# car_bt.net
KiCad netlist of a schematic drawn in EAGLE
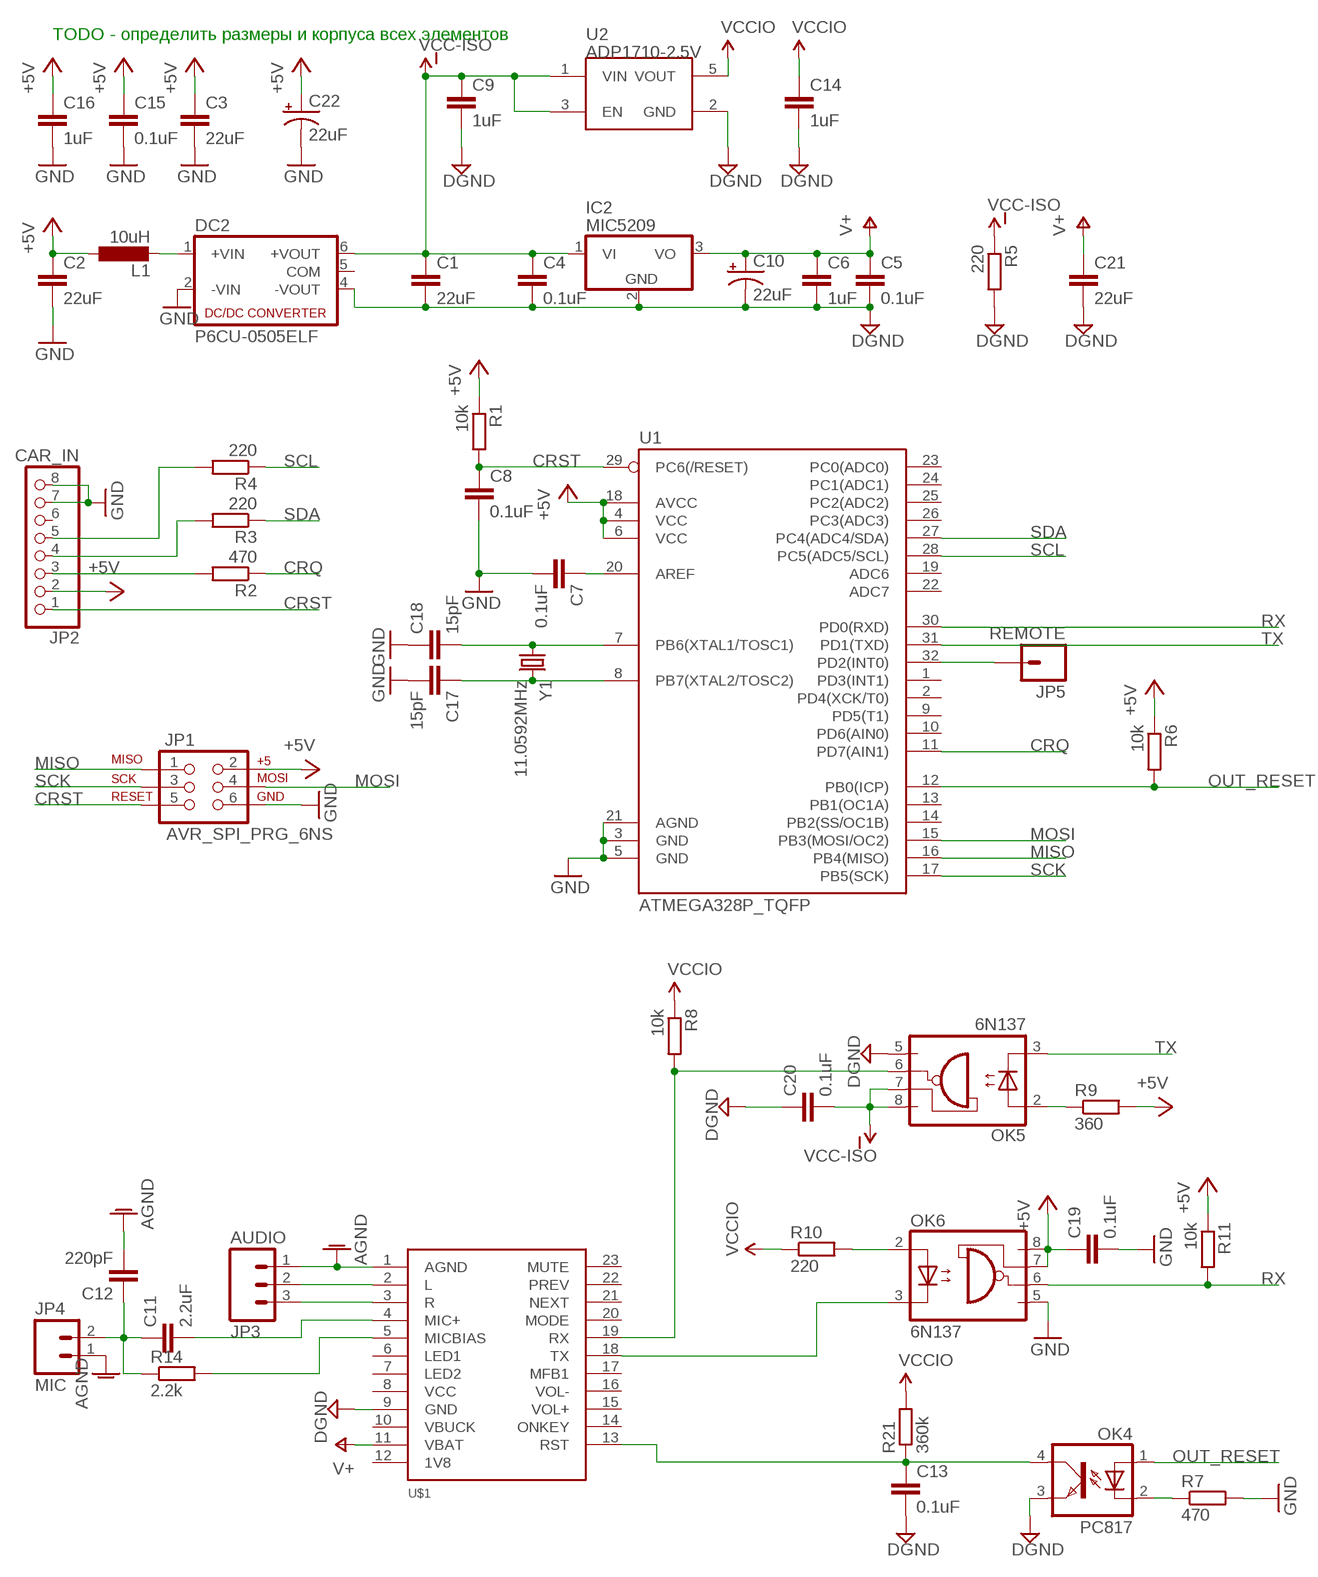
[diagram p0: schematic, sheet 1]

(export (version "E")
  (design (tool "Eeschema 10.0.6"))
  (components
    (comp (ref "C1")
      (value "22uF")
      (footprint "eagle-import:C1206")
      (libsource (lib "eagle-import") (part "C-EUC1206"))
    )
    (comp (ref "C2")
      (value "22uF")
      (footprint "eagle-import:C1206")
      (libsource (lib "eagle-import") (part "C-EUC1206"))
    )
    (comp (ref "C3")
      (value "22uF")
      (footprint "eagle-import:C1206")
      (libsource (lib "eagle-import") (part "C-EUC1206"))
    )
    (comp (ref "C4")
      (value "0.1uF")
      (footprint "eagle-import:C0805")
      (libsource (lib "eagle-import") (part "C-EUC0805"))
    )
    (comp (ref "C5")
      (value "0.1uF")
      (footprint "eagle-import:C0805")
      (libsource (lib "eagle-import") (part "C-EUC0805"))
    )
    (comp (ref "C6")
      (value "1uF")
      (footprint "eagle-import:C0805")
      (libsource (lib "eagle-import") (part "C-EUC0805"))
    )
    (comp (ref "C7")
      (value "0.1uF")
      (footprint "eagle-import:C0805")
      (libsource (lib "eagle-import") (part "C-EUC0805"))
    )
    (comp (ref "C8")
      (value "0.1uF")
      (footprint "eagle-import:C0805")
      (libsource (lib "eagle-import") (part "C-EUC0805"))
    )
    (comp (ref "C9")
      (value "1uF")
      (footprint "eagle-import:C0805")
      (libsource (lib "eagle-import") (part "C-EUC0805"))
    )
    (comp (ref "C10")
      (value "22uF")
      (footprint "eagle-import:EIA3528")
      (libsource (lib "eagle-import") (part "CAP_POL3528"))
    )
    (comp (ref "C11")
      (value "2.2uF")
      (footprint "eagle-import:C0805")
      (libsource (lib "eagle-import") (part "C-EUC0805"))
    )
    (comp (ref "C12")
      (value "220pF")
      (footprint "eagle-import:C0805")
      (libsource (lib "eagle-import") (part "C-EUC0805"))
    )
    (comp (ref "C13")
      (value "0.1uF")
      (footprint "eagle-import:C0805")
      (libsource (lib "eagle-import") (part "C-EUC0805"))
    )
    (comp (ref "C14")
      (value "1uF")
      (footprint "eagle-import:C0805")
      (libsource (lib "eagle-import") (part "C-EUC0805"))
    )
    (comp (ref "C15")
      (value "0.1uF")
      (footprint "eagle-import:C0805")
      (libsource (lib "eagle-import") (part "C-EUC0805"))
    )
    (comp (ref "C16")
      (value "1uF")
      (footprint "eagle-import:C0805")
      (libsource (lib "eagle-import") (part "C-EUC0805"))
    )
    (comp (ref "C17")
      (value "15pF")
      (footprint "eagle-import:C0805")
      (libsource (lib "eagle-import") (part "C-EUC0805"))
    )
    (comp (ref "C18")
      (value "15pF")
      (footprint "eagle-import:C0805")
      (libsource (lib "eagle-import") (part "C-EUC0805"))
    )
    (comp (ref "C19")
      (value "0.1uF")
      (footprint "eagle-import:C0805")
      (libsource (lib "eagle-import") (part "C-EUC0805"))
    )
    (comp (ref "C20")
      (value "0.1uF")
      (footprint "eagle-import:C0805")
      (libsource (lib "eagle-import") (part "C-EUC0805"))
    )
    (comp (ref "C21")
      (value "22uF")
      (footprint "eagle-import:C1206")
      (libsource (lib "eagle-import") (part "C-EUC1206"))
    )
    (comp (ref "C22")
      (value "22uF")
      (footprint "eagle-import:EIA3528")
      (libsource (lib "eagle-import") (part "CAP_POL3528"))
    )
    (comp (ref "DC2")
      (value "P6CU-0505ELF")
      (footprint "eagle-import:NMA")
      (fields (field (name "MF") "C & D TECHNOLOGIES, INC") (field (name "MPN") "NMA0515SC"))
      (libsource (lib "eagle-import") (part "NMA"))
    )
    (comp (ref "IC2")
      (value "MIC5209")
      (footprint "eagle-import:SOT223")
      (libsource (lib "eagle-import") (part "MCP1703DB"))
    )
    (comp (ref "JP1")
      (value "AVR_SPI_PRG_6NS")
      (footprint "eagle-import:2X3-NS")
      (libsource (lib "eagle-import") (part "AVR_SPI_PRG_6NS"))
    )
    (comp (ref "JP2")
      (value "CAR_IN")
      (footprint "eagle-import:1X08_90")
      (libsource (lib "eagle-import") (part "PINHD-1X8/90"))
    )
    (comp (ref "JP3")
      (value "AUDIO")
      (footprint "eagle-import:MOLEX-1X3")
      (libsource (lib "eagle-import") (part "M03POLAR"))
    )
    (comp (ref "JP4")
      (value "MIC")
      (footprint "eagle-import:MOLEX-1X2_LOCK")
      (libsource (lib "eagle-import") (part "M02POLAR_LOCK"))
    )
    (comp (ref "JP5")
      (value "REMOTE")
      (footprint "eagle-import:1X01_LONGPAD")
      (libsource (lib "eagle-import") (part "M01PTH_LONGPAD"))
    )
    (comp (ref "L1")
      (value "10uH")
      (footprint "eagle-import:L3216C")
      (libsource (lib "eagle-import") (part "L-EUL3216C"))
    )
    (comp (ref "OK4")
      (value "PC817")
      (footprint "eagle-import:DIL04")
      (fields (field (name "MPN") "PC817X4J000F"))
      (libsource (lib "eagle-import") (part "PC817"))
    )
    (comp (ref "OK5")
      (value "6N137")
      (footprint "eagle-import:DIL08")
      (libsource (lib "eagle-import") (part "6N137"))
    )
    (comp (ref "OK6")
      (value "6N137")
      (footprint "eagle-import:DIL08")
      (libsource (lib "eagle-import") (part "6N137"))
    )
    (comp (ref "R1")
      (value "10k")
      (footprint "eagle-import:R0805")
      (libsource (lib "eagle-import") (part "R-EU_R0805"))
    )
    (comp (ref "R2")
      (value "470")
      (footprint "eagle-import:R0805")
      (libsource (lib "eagle-import") (part "R-EU_R0805"))
    )
    (comp (ref "R3")
      (value "220")
      (footprint "eagle-import:R0805")
      (libsource (lib "eagle-import") (part "R-EU_R0805"))
    )
    (comp (ref "R4")
      (value "220")
      (footprint "eagle-import:R0805")
      (libsource (lib "eagle-import") (part "R-EU_R0805"))
    )
    (comp (ref "R5")
      (value "220")
      (footprint "eagle-import:R0805")
      (libsource (lib "eagle-import") (part "R-EU_R0805"))
    )
    (comp (ref "R6")
      (value "10k")
      (footprint "eagle-import:R0805")
      (libsource (lib "eagle-import") (part "R-EU_R0805"))
    )
    (comp (ref "R7")
      (value "470")
      (footprint "eagle-import:R0805")
      (libsource (lib "eagle-import") (part "R-EU_R0805"))
    )
    (comp (ref "R8")
      (value "10k")
      (footprint "eagle-import:R0805")
      (libsource (lib "eagle-import") (part "R-EU_R0805"))
    )
    (comp (ref "R9")
      (value "360")
      (footprint "eagle-import:R0805")
      (libsource (lib "eagle-import") (part "R-EU_R0805"))
    )
    (comp (ref "R10")
      (value "220")
      (footprint "eagle-import:R1206")
      (libsource (lib "eagle-import") (part "R-EU_R1206"))
    )
    (comp (ref "R11")
      (value "10k")
      (footprint "eagle-import:R0805")
      (libsource (lib "eagle-import") (part "R-EU_R0805"))
    )
    (comp (ref "R14")
      (value "2.2k")
      (footprint "eagle-import:R0805")
      (libsource (lib "eagle-import") (part "R-EU_R0805"))
    )
    (comp (ref "R21")
      (value "360k")
      (footprint "eagle-import:R0805")
      (libsource (lib "eagle-import") (part "R-EU_R0805"))
    )
    (comp (ref "U$1")
      (value "XS3868")
      (footprint "eagle-import:XS3868")
      (libsource (lib "eagle-import") (part "XS3868"))
    )
    (comp (ref "U1")
      (value "ATMEGA328P_TQFP")
      (footprint "eagle-import:TQFP32-08")
      (libsource (lib "eagle-import") (part "ATMEGA328P_TQFP"))
    )
    (comp (ref "U2")
      (value "ADP1710-2.5V")
      (footprint "eagle-import:SOT23-5")
      (libsource (lib "eagle-import") (part "ADP160"))
    )
    (comp (ref "Y1")
      (value "11.0592MHz")
      (footprint "eagle-import:HC49U-V")
      (libsource (lib "eagle-import") (part "CRYSTALHC49UV"))
    )
  )
  (nets
    (net (code "1") (name "+5V") (class "Default")
      (node (ref "C15") (pin "1") (pinfunction "1_1") (pintype "passive"))
      (node (ref "C16") (pin "1") (pinfunction "1_1") (pintype "passive"))
      (node (ref "C19") (pin "1") (pinfunction "1_1") (pintype "passive"))
      (node (ref "C2") (pin "1") (pinfunction "1_1") (pintype "passive"))
      (node (ref "C22") (pin "A") (pinfunction "+_A") (pintype "passive"))
      (node (ref "C3") (pin "1") (pinfunction "1_1") (pintype "passive"))
      (node (ref "JP1") (pin "2") (pinfunction "2_2") (pintype "passive"))
      (node (ref "JP2") (pin "2") (pinfunction "2_2") (pintype "passive"))
      (node (ref "L1") (pin "1") (pinfunction "1_1") (pintype "passive"))
      (node (ref "OK6") (pin "7") (pinfunction "VE_7") (pintype "passive"))
      (node (ref "OK6") (pin "8") (pinfunction "VCC_8") (pintype "passive"))
      (node (ref "R1") (pin "1") (pinfunction "1_1") (pintype "passive"))
      (node (ref "R11") (pin "1") (pinfunction "1_1") (pintype "passive"))
      (node (ref "R6") (pin "1") (pinfunction "1_1") (pintype "passive"))
      (node (ref "R9") (pin "2") (pinfunction "2_2") (pintype "passive"))
      (node (ref "U1") (pin "18") (pinfunction "AVCC_18") (pintype "bidirectional"))
      (node (ref "U1") (pin "4") (pinfunction "VCC_4") (pintype "bidirectional"))
      (node (ref "U1") (pin "6") (pinfunction "VCC_6") (pintype "bidirectional"))
    )
    (net (code "2") (name "/CRQ") (class "Default")
      (node (ref "R2") (pin "1") (pinfunction "1_1") (pintype "passive"))
      (node (ref "U1") (pin "11") (pinfunction "PD7(AIN1)_11") (pintype "bidirectional"))
    )
    (net (code "3") (name "/CRST") (class "Default")
      (node (ref "C8") (pin "1") (pinfunction "1_1") (pintype "passive"))
      (node (ref "JP1") (pin "5") (pinfunction "5_5") (pintype "passive"))
      (node (ref "JP2") (pin "1") (pinfunction "1_1") (pintype "passive"))
      (node (ref "R1") (pin "2") (pinfunction "2_2") (pintype "passive"))
      (node (ref "U1") (pin "29") (pinfunction "PC6(/RESET)_29") (pintype "bidirectional"))
    )
    (net (code "4") (name "/MISO") (class "Default")
      (node (ref "JP1") (pin "1") (pinfunction "1_1") (pintype "passive"))
      (node (ref "U1") (pin "16") (pinfunction "PB4(MISO)_16") (pintype "bidirectional"))
    )
    (net (code "5") (name "/MOSI") (class "Default")
      (node (ref "JP1") (pin "4") (pinfunction "4_4") (pintype "passive"))
      (node (ref "U1") (pin "15") (pinfunction "PB3(MOSI/OC2)_15") (pintype "bidirectional"))
    )
    (net (code "6") (name "/OUT_RESET") (class "Default")
      (node (ref "OK4") (pin "1") (pinfunction "A_1") (pintype "passive"))
      (node (ref "R6") (pin "2") (pinfunction "2_2") (pintype "passive"))
      (node (ref "U1") (pin "12") (pinfunction "PB0(ICP)_12") (pintype "bidirectional"))
    )
    (net (code "7") (name "/RX") (class "Default")
      (node (ref "OK6") (pin "6") (pinfunction "VO_6") (pintype "passive"))
      (node (ref "R11") (pin "2") (pinfunction "2_2") (pintype "passive"))
      (node (ref "U1") (pin "30") (pinfunction "PD0(RXD)_30") (pintype "bidirectional"))
    )
    (net (code "8") (name "/SCK") (class "Default")
      (node (ref "JP1") (pin "3") (pinfunction "3_3") (pintype "passive"))
      (node (ref "U1") (pin "17") (pinfunction "PB5(SCK)_17") (pintype "bidirectional"))
    )
    (net (code "9") (name "/SCL") (class "Default")
      (node (ref "R4") (pin "1") (pinfunction "1_1") (pintype "passive"))
      (node (ref "U1") (pin "28") (pinfunction "PC5(ADC5/SCL)_28") (pintype "bidirectional"))
    )
    (net (code "10") (name "/SDA") (class "Default")
      (node (ref "R3") (pin "1") (pinfunction "1_1") (pintype "passive"))
      (node (ref "U1") (pin "27") (pinfunction "PC4(ADC4/SDA)_27") (pintype "bidirectional"))
    )
    (net (code "11") (name "/TX") (class "Default")
      (node (ref "OK5") (pin "3") (pinfunction "C_3") (pintype "passive"))
      (node (ref "U1") (pin "31") (pinfunction "PD1(TXD)_31") (pintype "bidirectional"))
    )
    (net (code "12") (name "AGND") (class "Default")
      (node (ref "C12") (pin "2") (pinfunction "2_2") (pintype "passive"))
      (node (ref "JP3") (pin "1") (pinfunction "1_1") (pintype "passive"))
      (node (ref "JP4") (pin "1") (pinfunction "1_1") (pintype "passive"))
      (node (ref "U$1") (pin "1") (pinfunction "AGND_1") (pintype "bidirectional"))
    )
    (net (code "13") (name "DGND") (class "Default")
      (node (ref "C1") (pin "2") (pinfunction "2_2") (pintype "passive"))
      (node (ref "C10") (pin "C") (pinfunction "-_C") (pintype "passive"))
      (node (ref "C13") (pin "2") (pinfunction "2_2") (pintype "passive"))
      (node (ref "C14") (pin "2") (pinfunction "2_2") (pintype "passive"))
      (node (ref "C20") (pin "1") (pinfunction "1_1") (pintype "passive"))
      (node (ref "C21") (pin "2") (pinfunction "2_2") (pintype "passive"))
      (node (ref "C4") (pin "2") (pinfunction "2_2") (pintype "passive"))
      (node (ref "C5") (pin "2") (pinfunction "2_2") (pintype "passive"))
      (node (ref "C6") (pin "2") (pinfunction "2_2") (pintype "passive"))
      (node (ref "C9") (pin "2") (pinfunction "2_2") (pintype "passive"))
      (node (ref "DC2") (pin "4") (pinfunction "-VOUT_4") (pintype "passive"))
      (node (ref "IC2") (pin "2") (pinfunction "GND_2") (pintype "passive"))
      (node (ref "OK4") (pin "3") (pinfunction "EMIT_3") (pintype "passive"))
      (node (ref "OK5") (pin "5") (pinfunction "GND_5") (pintype "passive"))
      (node (ref "R5") (pin "2") (pinfunction "2_2") (pintype "passive"))
      (node (ref "U$1") (pin "9") (pinfunction "GND_9") (pintype "bidirectional"))
      (node (ref "U2") (pin "2") (pinfunction "GND_2") (pintype "bidirectional"))
    )
    (net (code "14") (name "GND") (class "Default")
      (node (ref "C15") (pin "2") (pinfunction "2_2") (pintype "passive"))
      (node (ref "C16") (pin "2") (pinfunction "2_2") (pintype "passive"))
      (node (ref "C17") (pin "2") (pinfunction "2_2") (pintype "passive"))
      (node (ref "C18") (pin "1") (pinfunction "1_1") (pintype "passive"))
      (node (ref "C19") (pin "2") (pinfunction "2_2") (pintype "passive"))
      (node (ref "C2") (pin "2") (pinfunction "2_2") (pintype "passive"))
      (node (ref "C22") (pin "C") (pinfunction "-_C") (pintype "passive"))
      (node (ref "C3") (pin "2") (pinfunction "2_2") (pintype "passive"))
      (node (ref "C7") (pin "2") (pinfunction "2_2") (pintype "passive"))
      (node (ref "C8") (pin "2") (pinfunction "2_2") (pintype "passive"))
      (node (ref "DC2") (pin "2") (pinfunction "-VIN_2") (pintype "passive"))
      (node (ref "JP1") (pin "6") (pinfunction "6_6") (pintype "passive"))
      (node (ref "JP2") (pin "7") (pinfunction "7_7") (pintype "passive"))
      (node (ref "JP2") (pin "8") (pinfunction "8_8") (pintype "passive"))
      (node (ref "OK6") (pin "5") (pinfunction "GND_5") (pintype "passive"))
      (node (ref "R7") (pin "2") (pinfunction "2_2") (pintype "passive"))
      (node (ref "U1") (pin "21") (pinfunction "AGND_21") (pintype "bidirectional"))
      (node (ref "U1") (pin "3") (pinfunction "GND_3") (pintype "bidirectional"))
      (node (ref "U1") (pin "5") (pinfunction "GND_5") (pintype "bidirectional"))
    )
    (net (code "15") (name "Net-(C11-Pad1)") (class "Default")
      (node (ref "C11") (pin "1") (pinfunction "1_1") (pintype "passive"))
      (node (ref "C12") (pin "1") (pinfunction "1_1") (pintype "passive"))
      (node (ref "JP4") (pin "2") (pinfunction "2_2") (pintype "passive"))
      (node (ref "R14") (pin "1") (pinfunction "1_1") (pintype "passive"))
    )
    (net (code "16") (name "Net-(DC2-+VIN)") (class "Default")
      (node (ref "DC2") (pin "1") (pinfunction "+VIN_1") (pintype "passive"))
      (node (ref "L1") (pin "2") (pinfunction "2_2") (pintype "passive"))
    )
    (net (code "17") (name "Net-(JP2-Pad3)") (class "Default")
      (node (ref "JP2") (pin "3") (pinfunction "3_3") (pintype "passive"))
      (node (ref "R2") (pin "2") (pinfunction "2_2") (pintype "passive"))
    )
    (net (code "18") (name "Net-(JP2-Pad4)") (class "Default")
      (node (ref "JP2") (pin "4") (pinfunction "4_4") (pintype "passive"))
      (node (ref "R3") (pin "2") (pinfunction "2_2") (pintype "passive"))
    )
    (net (code "19") (name "Net-(JP2-Pad5)") (class "Default")
      (node (ref "JP2") (pin "5") (pinfunction "5_5") (pintype "passive"))
      (node (ref "R4") (pin "2") (pinfunction "2_2") (pintype "passive"))
    )
    (net (code "20") (name "Net-(OK4-C)") (class "Default")
      (node (ref "OK4") (pin "2") (pinfunction "C_2") (pintype "passive"))
      (node (ref "R7") (pin "1") (pinfunction "1_1") (pintype "passive"))
    )
    (net (code "21") (name "Net-(OK4-COL)") (class "Default")
      (node (ref "C13") (pin "1") (pinfunction "1_1") (pintype "passive"))
      (node (ref "OK4") (pin "4") (pinfunction "COL_4") (pintype "passive"))
      (node (ref "R21") (pin "1") (pinfunction "1_1") (pintype "passive"))
      (node (ref "U$1") (pin "13") (pinfunction "RST_13") (pintype "bidirectional"))
    )
    (net (code "22") (name "Net-(OK5-A)") (class "Default")
      (node (ref "OK5") (pin "2") (pinfunction "A_2") (pintype "passive"))
      (node (ref "R9") (pin "1") (pinfunction "1_1") (pintype "passive"))
    )
    (net (code "23") (name "Net-(OK5-VO)") (class "Default")
      (node (ref "OK5") (pin "6") (pinfunction "VO_6") (pintype "passive"))
      (node (ref "R8") (pin "2") (pinfunction "2_2") (pintype "passive"))
      (node (ref "U$1") (pin "19") (pinfunction "RX_19") (pintype "bidirectional"))
    )
    (net (code "24") (name "Net-(OK6-A)") (class "Default")
      (node (ref "OK6") (pin "2") (pinfunction "A_2") (pintype "passive"))
      (node (ref "R10") (pin "2") (pinfunction "2_2") (pintype "passive"))
    )
    (net (code "25") (name "Net-(OK6-C)") (class "Default")
      (node (ref "OK6") (pin "3") (pinfunction "C_3") (pintype "passive"))
      (node (ref "U$1") (pin "18") (pinfunction "TX_18") (pintype "bidirectional"))
    )
    (net (code "26") (name "Net-(U$1-L)") (class "Default")
      (node (ref "JP3") (pin "2") (pinfunction "2_2") (pintype "passive"))
      (node (ref "U$1") (pin "2") (pinfunction "L_2") (pintype "bidirectional"))
    )
    (net (code "27") (name "Net-(U$1-MIC+)") (class "Default")
      (node (ref "C11") (pin "2") (pinfunction "2_2") (pintype "passive"))
      (node (ref "U$1") (pin "4") (pinfunction "MIC+_4") (pintype "bidirectional"))
    )
    (net (code "28") (name "Net-(U$1-MICBIAS)") (class "Default")
      (node (ref "R14") (pin "2") (pinfunction "2_2") (pintype "passive"))
      (node (ref "U$1") (pin "5") (pinfunction "MICBIAS_5") (pintype "bidirectional"))
    )
    (net (code "29") (name "Net-(U$1-R)") (class "Default")
      (node (ref "JP3") (pin "3") (pinfunction "3_3") (pintype "passive"))
      (node (ref "U$1") (pin "3") (pinfunction "R_3") (pintype "bidirectional"))
    )
    (net (code "30") (name "Net-(U1-AREF)") (class "Default")
      (node (ref "C7") (pin "1") (pinfunction "1_1") (pintype "passive"))
      (node (ref "U1") (pin "20") (pinfunction "AREF_20") (pintype "bidirectional"))
    )
    (net (code "31") (name "Net-(U1-PB6(XTAL1{slash}TOSC1))") (class "Default")
      (node (ref "C18") (pin "2") (pinfunction "2_2") (pintype "passive"))
      (node (ref "U1") (pin "7") (pinfunction "PB6(XTAL1/TOSC1)_7") (pintype "bidirectional"))
      (node (ref "Y1") (pin "1") (pinfunction "1_1") (pintype "passive"))
    )
    (net (code "32") (name "Net-(U1-PB7(XTAL2{slash}TOSC2))") (class "Default")
      (node (ref "C17") (pin "1") (pinfunction "1_1") (pintype "passive"))
      (node (ref "U1") (pin "8") (pinfunction "PB7(XTAL2/TOSC2)_8") (pintype "bidirectional"))
      (node (ref "Y1") (pin "2") (pinfunction "2_2") (pintype "passive"))
    )
    (net (code "33") (name "Net-(U1-PD2(INT0))") (class "Default")
      (node (ref "JP5") (pin "1") (pinfunction "1_1") (pintype "passive"))
      (node (ref "U1") (pin "32") (pinfunction "PD2(INT0)_32") (pintype "bidirectional"))
    )
    (net (code "34") (name "V+") (class "Default")
      (node (ref "C10") (pin "A") (pinfunction "+_A") (pintype "passive"))
      (node (ref "C21") (pin "1") (pinfunction "1_1") (pintype "passive"))
      (node (ref "C5") (pin "1") (pinfunction "1_1") (pintype "passive"))
      (node (ref "C6") (pin "1") (pinfunction "1_1") (pintype "passive"))
      (node (ref "IC2") (pin "3") (pinfunction "VO_3") (pintype "passive"))
      (node (ref "U$1") (pin "11") (pinfunction "VBAT_11") (pintype "bidirectional"))
    )
    (net (code "35") (name "VCC-ISO") (class "Default")
      (node (ref "C1") (pin "1") (pinfunction "1_1") (pintype "passive"))
      (node (ref "C20") (pin "2") (pinfunction "2_2") (pintype "passive"))
      (node (ref "C4") (pin "1") (pinfunction "1_1") (pintype "passive"))
      (node (ref "C9") (pin "1") (pinfunction "1_1") (pintype "passive"))
      (node (ref "DC2") (pin "6") (pinfunction "+VOUT_6") (pintype "passive"))
      (node (ref "IC2") (pin "1") (pinfunction "VI_1") (pintype "input"))
      (node (ref "OK5") (pin "7") (pinfunction "VE_7") (pintype "passive"))
      (node (ref "OK5") (pin "8") (pinfunction "VCC_8") (pintype "passive"))
      (node (ref "R5") (pin "1") (pinfunction "1_1") (pintype "passive"))
      (node (ref "U2") (pin "1") (pinfunction "VIN_1") (pintype "bidirectional"))
      (node (ref "U2") (pin "3") (pinfunction "EN_3") (pintype "bidirectional"))
    )
    (net (code "36") (name "VCCIO") (class "Default")
      (node (ref "C14") (pin "1") (pinfunction "1_1") (pintype "passive"))
      (node (ref "R10") (pin "1") (pinfunction "1_1") (pintype "passive"))
      (node (ref "R21") (pin "2") (pinfunction "2_2") (pintype "passive"))
      (node (ref "R8") (pin "1") (pinfunction "1_1") (pintype "passive"))
      (node (ref "U2") (pin "5") (pinfunction "VOUT_5") (pintype "bidirectional"))
    )
    (net (code "37") (name "unconnected-(DC2-COM-Pad5)") (class "Default")
      (node (ref "DC2") (pin "5") (pinfunction "COM_5") (pintype "passive"))
    )
    (net (code "38") (name "unconnected-(JP2-Pad6)") (class "Default")
      (node (ref "JP2") (pin "6") (pinfunction "6_6") (pintype "passive"))
    )
    (net (code "39") (name "unconnected-(U$1-1V8-Pad12)") (class "Default")
      (node (ref "U$1") (pin "12") (pinfunction "1V8_12") (pintype "bidirectional"))
    )
    (net (code "40") (name "unconnected-(U$1-LED1-Pad6)") (class "Default")
      (node (ref "U$1") (pin "6") (pinfunction "LED1_6") (pintype "bidirectional"))
    )
    (net (code "41") (name "unconnected-(U$1-LED2-Pad7)") (class "Default")
      (node (ref "U$1") (pin "7") (pinfunction "LED2_7") (pintype "bidirectional"))
    )
    (net (code "42") (name "unconnected-(U$1-MFB1-Pad17)") (class "Default")
      (node (ref "U$1") (pin "17") (pinfunction "MFB1_17") (pintype "bidirectional"))
    )
    (net (code "43") (name "unconnected-(U$1-MODE-Pad20)") (class "Default")
      (node (ref "U$1") (pin "20") (pinfunction "MODE_20") (pintype "bidirectional"))
    )
    (net (code "44") (name "unconnected-(U$1-MUTE-Pad23)") (class "Default")
      (node (ref "U$1") (pin "23") (pinfunction "MUTE_23") (pintype "bidirectional"))
    )
    (net (code "45") (name "unconnected-(U$1-NEXT-Pad21)") (class "Default")
      (node (ref "U$1") (pin "21") (pinfunction "NEXT_21") (pintype "bidirectional"))
    )
    (net (code "46") (name "unconnected-(U$1-ONKEY-Pad14)") (class "Default")
      (node (ref "U$1") (pin "14") (pinfunction "ONKEY_14") (pintype "bidirectional"))
    )
    (net (code "47") (name "unconnected-(U$1-PREV-Pad22)") (class "Default")
      (node (ref "U$1") (pin "22") (pinfunction "PREV_22") (pintype "bidirectional"))
    )
    (net (code "48") (name "unconnected-(U$1-VBUCK-Pad10)") (class "Default")
      (node (ref "U$1") (pin "10") (pinfunction "VBUCK_10") (pintype "bidirectional"))
    )
    (net (code "49") (name "unconnected-(U$1-VCC-Pad8)") (class "Default")
      (node (ref "U$1") (pin "8") (pinfunction "VCC_8") (pintype "bidirectional"))
    )
    (net (code "50") (name "unconnected-(U$1-VOL+-Pad15)") (class "Default")
      (node (ref "U$1") (pin "15") (pinfunction "VOL+_15") (pintype "bidirectional"))
    )
    (net (code "51") (name "unconnected-(U$1-VOL--Pad16)") (class "Default")
      (node (ref "U$1") (pin "16") (pinfunction "VOL-_16") (pintype "bidirectional"))
    )
    (net (code "52") (name "unconnected-(U1-ADC6-Pad19)") (class "Default")
      (node (ref "U1") (pin "19") (pinfunction "ADC6_19") (pintype "bidirectional"))
    )
    (net (code "53") (name "unconnected-(U1-ADC7-Pad22)") (class "Default")
      (node (ref "U1") (pin "22") (pinfunction "ADC7_22") (pintype "bidirectional"))
    )
    (net (code "54") (name "unconnected-(U1-PB1(OC1A)-Pad13)") (class "Default")
      (node (ref "U1") (pin "13") (pinfunction "PB1(OC1A)_13") (pintype "bidirectional"))
    )
    (net (code "55") (name "unconnected-(U1-PB2(SS{slash}OC1B)-Pad14)") (class "Default")
      (node (ref "U1") (pin "14") (pinfunction "PB2(SS/OC1B)_14") (pintype "bidirectional"))
    )
    (net (code "56") (name "unconnected-(U1-PC0(ADC0)-Pad23)") (class "Default")
      (node (ref "U1") (pin "23") (pinfunction "PC0(ADC0)_23") (pintype "bidirectional"))
    )
    (net (code "57") (name "unconnected-(U1-PC1(ADC1)-Pad24)") (class "Default")
      (node (ref "U1") (pin "24") (pinfunction "PC1(ADC1)_24") (pintype "bidirectional"))
    )
    (net (code "58") (name "unconnected-(U1-PC2(ADC2)-Pad25)") (class "Default")
      (node (ref "U1") (pin "25") (pinfunction "PC2(ADC2)_25") (pintype "bidirectional"))
    )
    (net (code "59") (name "unconnected-(U1-PC3(ADC3)-Pad26)") (class "Default")
      (node (ref "U1") (pin "26") (pinfunction "PC3(ADC3)_26") (pintype "bidirectional"))
    )
    (net (code "60") (name "unconnected-(U1-PD3(INT1)-Pad1)") (class "Default")
      (node (ref "U1") (pin "1") (pinfunction "PD3(INT1)_1") (pintype "bidirectional"))
    )
    (net (code "61") (name "unconnected-(U1-PD4(XCK{slash}T0)-Pad2)") (class "Default")
      (node (ref "U1") (pin "2") (pinfunction "PD4(XCK/T0)_2") (pintype "bidirectional"))
    )
    (net (code "62") (name "unconnected-(U1-PD5(T1)-Pad9)") (class "Default")
      (node (ref "U1") (pin "9") (pinfunction "PD5(T1)_9") (pintype "bidirectional"))
    )
    (net (code "63") (name "unconnected-(U1-PD6(AIN0)-Pad10)") (class "Default")
      (node (ref "U1") (pin "10") (pinfunction "PD6(AIN0)_10") (pintype "bidirectional"))
    )
  )
)
